# Sheet_HAT_GPIO_And_Analog_for_PI5.net
KiCad netlist of a schematic drawn in Altium Designer
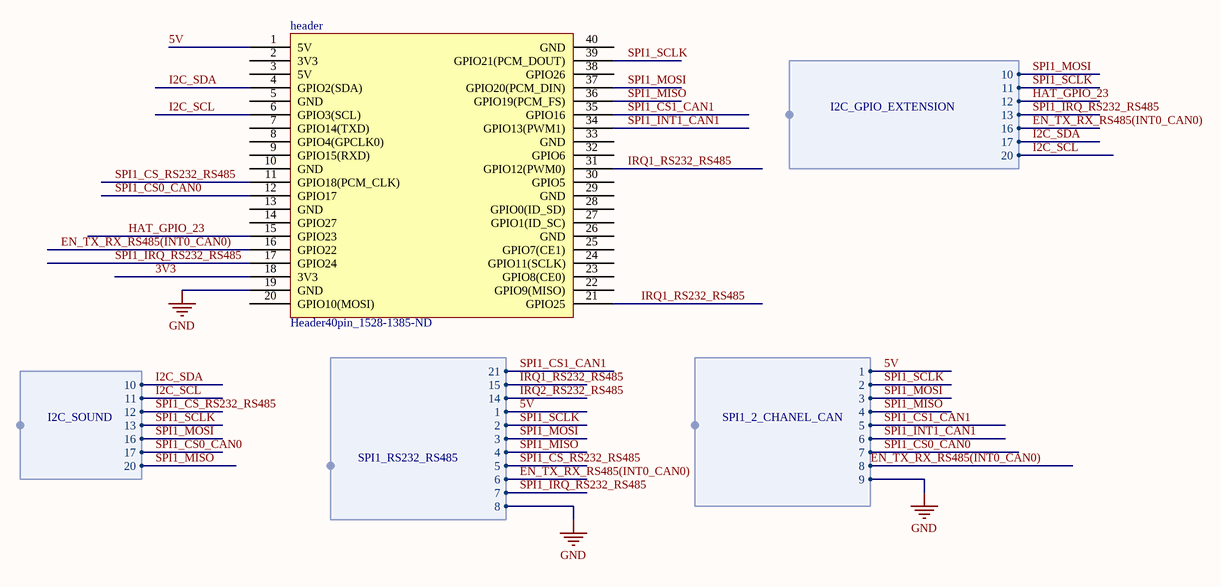
[diagram p0: Sheet_HAT_GPIO_And_Analog_for_PI5.SchDoc]

(export (version "E")
  (design (tool "Eeschema 10.0.6"))
  (components
    (comp (ref "header")
      (value "Header40pin_1528-1385-ND")
      (footprint "RHDR40W60P254_2X20_5100X500X2300P")
      (libsource (lib "Integrated_Library1") (part "Header40pin_1528-1385-ND"))
    )
  )
  (nets
    (net (code "1") (name "/3V3") (class "Default")
      (node (ref "header") (pin "18") (pinfunction "3V3_18") (pintype "passive"))
    )
    (net (code "2") (name "/5V") (class "Default")
      (node (ref "header") (pin "1") (pinfunction "5V_1") (pintype "passive"))
    )
    (net (code "3") (name "/EN_TX_RX_RS485(INT0_CAN0)") (class "Default")
      (node (ref "header") (pin "16") (pinfunction "GPIO22_16") (pintype "passive"))
    )
    (net (code "4") (name "/HAT_GPIO_23") (class "Default")
      (node (ref "header") (pin "15") (pinfunction "GPIO23_15") (pintype "passive"))
    )
    (net (code "5") (name "/I2C_SCL") (class "Default")
      (node (ref "header") (pin "6") (pinfunction "GPIO3(SCL)_6") (pintype "passive"))
    )
    (net (code "6") (name "/I2C_SDA") (class "Default")
      (node (ref "header") (pin "4") (pinfunction "GPIO2(SDA)_4") (pintype "passive"))
    )
    (net (code "7") (name "/IRQ1_RS232_RS485") (class "Default")
      (node (ref "header") (pin "21") (pinfunction "GPIO25_21") (pintype "passive"))
      (node (ref "header") (pin "31") (pinfunction "GPIO12(PWM0)_31") (pintype "passive"))
    )
    (net (code "9") (name "/SPI1_CS0_CAN0") (class "Default")
      (node (ref "header") (pin "12") (pinfunction "GPIO17_12") (pintype "passive"))
    )
    (net (code "10") (name "/SPI1_CS1_CAN1") (class "Default")
      (node (ref "header") (pin "35") (pinfunction "GPIO16_35") (pintype "passive"))
    )
    (net (code "11") (name "/SPI1_CS_RS232_RS485") (class "Default")
      (node (ref "header") (pin "11") (pinfunction "GPIO18(PCM_CLK)_11") (pintype "passive"))
    )
    (net (code "12") (name "/SPI1_INT1_CAN1") (class "Default")
      (node (ref "header") (pin "34") (pinfunction "GPIO13(PWM1)_34") (pintype "passive"))
    )
    (net (code "13") (name "/SPI1_IRQ_RS232_RS485") (class "Default")
      (node (ref "header") (pin "17") (pinfunction "GPIO24_17") (pintype "passive"))
    )
    (net (code "14") (name "/SPI1_MISO") (class "Default")
      (node (ref "header") (pin "36") (pinfunction "GPIO19(PCM_FS)_36") (pintype "passive"))
    )
    (net (code "15") (name "/SPI1_MOSI") (class "Default")
      (node (ref "header") (pin "37") (pinfunction "GPIO20(PCM_DIN)_37") (pintype "passive"))
    )
    (net (code "16") (name "/SPI1_SCLK") (class "Default")
      (node (ref "header") (pin "39") (pinfunction "GPIO21(PCM_DOUT)_39") (pintype "passive"))
    )
    (net (code "17") (name "GND") (class "Default")
      (node (ref "header") (pin "19") (pinfunction "GND_19") (pintype "passive"))
    )
    (net (code "18") (name "unconnected-(header-3V3-Pad2)") (class "Default")
      (node (ref "header") (pin "2") (pinfunction "3V3_2") (pintype "passive"))
    )
    (net (code "19") (name "unconnected-(header-5V-Pad3)") (class "Default")
      (node (ref "header") (pin "3") (pinfunction "5V_3") (pintype "passive"))
    )
    (net (code "20") (name "unconnected-(header-GND-Pad5)") (class "Default")
      (node (ref "header") (pin "5") (pinfunction "GND_5") (pintype "passive"))
    )
    (net (code "21") (name "unconnected-(header-GND-Pad10)") (class "Default")
      (node (ref "header") (pin "10") (pinfunction "GND_10") (pintype "passive"))
    )
    (net (code "22") (name "unconnected-(header-GND-Pad13)") (class "Default")
      (node (ref "header") (pin "13") (pinfunction "GND_13") (pintype "passive"))
    )
    (net (code "23") (name "unconnected-(header-GND-Pad26)") (class "Default")
      (node (ref "header") (pin "26") (pinfunction "GND_26") (pintype "passive"))
    )
    (net (code "24") (name "unconnected-(header-GND-Pad29)") (class "Default")
      (node (ref "header") (pin "29") (pinfunction "GND_29") (pintype "passive"))
    )
    (net (code "25") (name "unconnected-(header-GND-Pad33)") (class "Default")
      (node (ref "header") (pin "33") (pinfunction "GND_33") (pintype "passive"))
    )
    (net (code "26") (name "unconnected-(header-GND-Pad40)") (class "Default")
      (node (ref "header") (pin "40") (pinfunction "GND_40") (pintype "passive"))
    )
    (net (code "27") (name "unconnected-(header-GPIO0(ID_SD)-Pad28)") (class "Default")
      (node (ref "header") (pin "28") (pinfunction "GPIO0(ID_SD)_28") (pintype "passive"))
    )
    (net (code "28") (name "unconnected-(header-GPIO1(ID_SC)-Pad27)") (class "Default")
      (node (ref "header") (pin "27") (pinfunction "GPIO1(ID_SC)_27") (pintype "passive"))
    )
    (net (code "29") (name "unconnected-(header-GPIO4(GPCLK0)-Pad8)") (class "Default")
      (node (ref "header") (pin "8") (pinfunction "GPIO4(GPCLK0)_8") (pintype "passive"))
    )
    (net (code "30") (name "unconnected-(header-GPIO5-Pad30)") (class "Default")
      (node (ref "header") (pin "30") (pinfunction "GPIO5_30") (pintype "passive"))
    )
    (net (code "31") (name "unconnected-(header-GPIO6-Pad32)") (class "Default")
      (node (ref "header") (pin "32") (pinfunction "GPIO6_32") (pintype "passive"))
    )
    (net (code "32") (name "unconnected-(header-GPIO7(CE1)-Pad25)") (class "Default")
      (node (ref "header") (pin "25") (pinfunction "GPIO7(CE1)_25") (pintype "passive"))
    )
    (net (code "33") (name "unconnected-(header-GPIO8(CE0)-Pad23)") (class "Default")
      (node (ref "header") (pin "23") (pinfunction "GPIO8(CE0)_23") (pintype "passive"))
    )
    (net (code "34") (name "unconnected-(header-GPIO9(MISO)-Pad22)") (class "Default")
      (node (ref "header") (pin "22") (pinfunction "GPIO9(MISO)_22") (pintype "passive"))
    )
    (net (code "35") (name "unconnected-(header-GPIO10(MOSI)-Pad20)") (class "Default")
      (node (ref "header") (pin "20") (pinfunction "GPIO10(MOSI)_20") (pintype "passive"))
    )
    (net (code "36") (name "unconnected-(header-GPIO11(SCLK)-Pad24)") (class "Default")
      (node (ref "header") (pin "24") (pinfunction "GPIO11(SCLK)_24") (pintype "passive"))
    )
    (net (code "37") (name "unconnected-(header-GPIO14(TXD)-Pad7)") (class "Default")
      (node (ref "header") (pin "7") (pinfunction "GPIO14(TXD)_7") (pintype "passive"))
    )
    (net (code "38") (name "unconnected-(header-GPIO15(RXD)-Pad9)") (class "Default")
      (node (ref "header") (pin "9") (pinfunction "GPIO15(RXD)_9") (pintype "passive"))
    )
    (net (code "39") (name "unconnected-(header-GPIO26-Pad38)") (class "Default")
      (node (ref "header") (pin "38") (pinfunction "GPIO26_38") (pintype "passive"))
    )
    (net (code "40") (name "unconnected-(header-GPIO27-Pad14)") (class "Default")
      (node (ref "header") (pin "14") (pinfunction "GPIO27_14") (pintype "passive"))
    )
  )
)
